# ShutdownSegement.net
KiCad netlist of a schematic drawn in Altium Designer
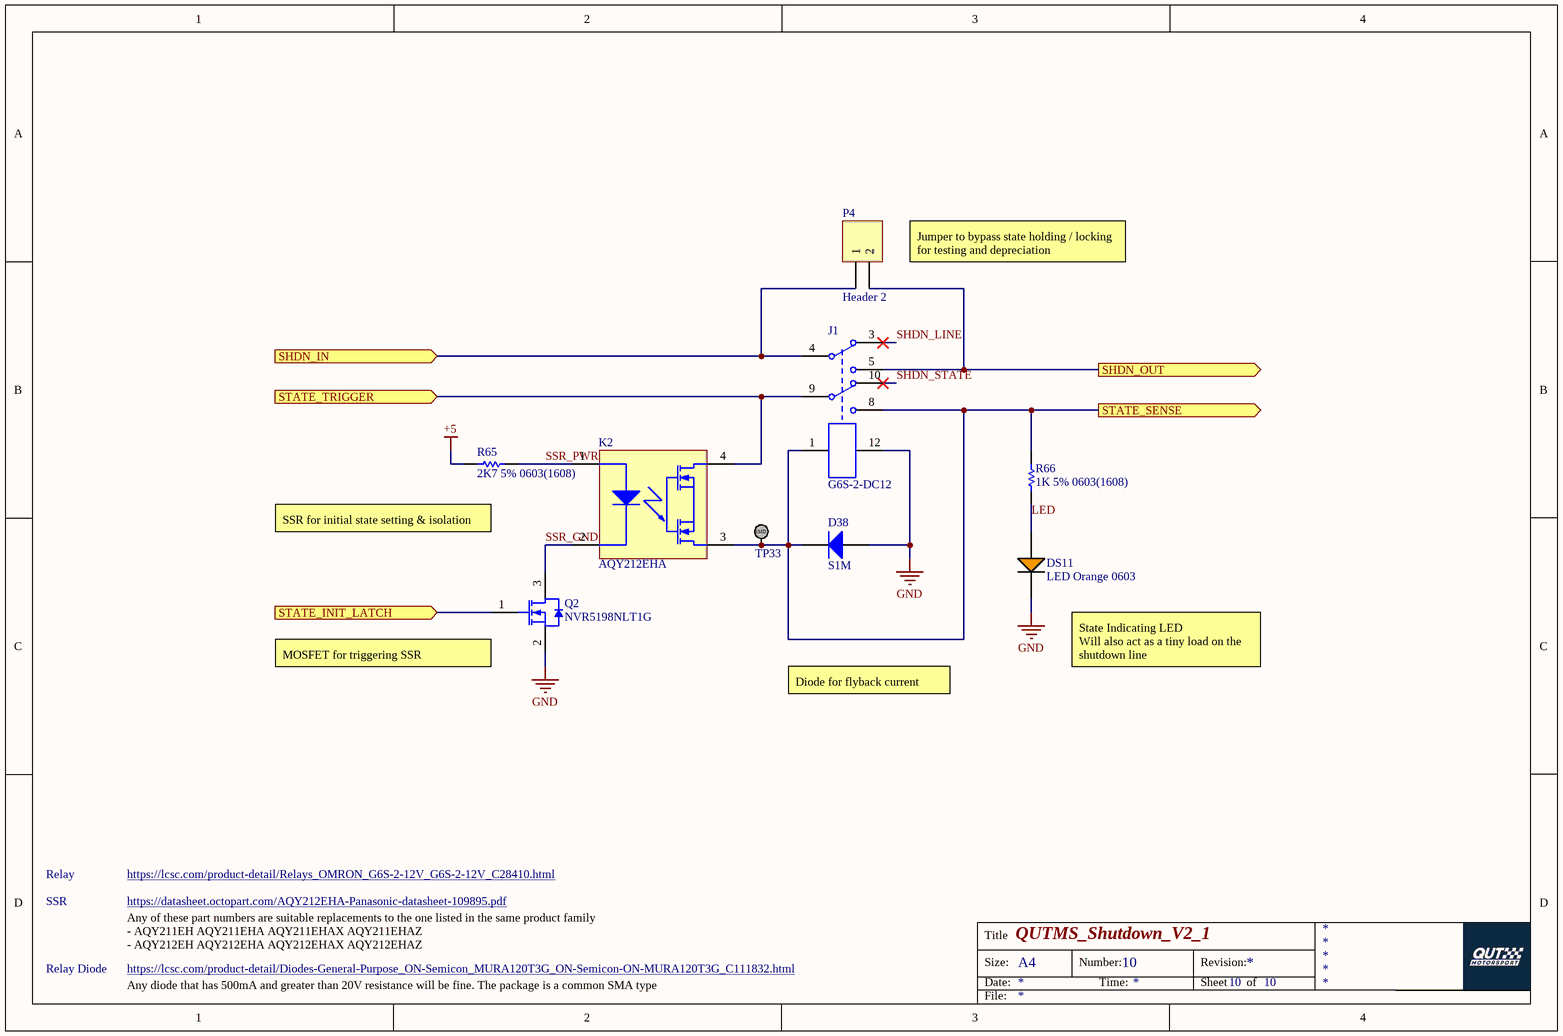
[diagram p0: ShutdownSegement.SchDoc]

(export (version "E")
  (design (tool "Eeschema 10.0.6"))
  (components
    (comp (ref "D38")
      (value "S1M")
      (footprint "FAIR-DO-214AC-2_V")
      (description "General Purpose Rectifier, 1 A, 1000 V, -55 to 150 degC, 2-Pin DO-214AC, RoHS, Tape and Reel")
      (fields (field (name "MANUFACTURER") "Fairchild"))
      (libsource (lib "Altium Content Vault") (part "D-AK-2"))
    )
    (comp (ref "DS11")
      (value "LED Orange 0603")
      (footprint "LED ORANGE 0603")
      (libsource (lib "QUTMS_LEDLibrary") (part "LED ORANGE 0603"))
    )
    (comp (ref "J1")
      (value "G6S-2-DC12")
      (footprint "G6S-2")
      (description "Telecom Non Latching 12VDC DPDT 2A Through Hole Relays RoHS")
      (libsource (lib "QUTMS_RelayLibrary") (part "G6S-2-DC12"))
    )
    (comp (ref "K2")
      (value "AQY212EHA")
      (footprint "PNSC-DIP4(SMT)_V")
      (fields (field (name "MANUFACTURER") "Panasonic"))
      (libsource (lib "Altium Content Vault") (part "PNSC-AQY212EH-DIP4"))
    )
    (comp (ref "P4")
      (value "Header 2")
      (footprint "HDR1X2")
      (description "Header, 2-Pin")
      (fields (field (name "PUBLISHER") "Altium Limited"))
      (libsource (lib "Miscellaneous Connectors") (part "Header 2"))
    )
    (comp (ref "Q2")
      (value "NVR5198NLT1G")
      (footprint "ONSC-SOT-23-3-318-08_V")
      (description "Power MOSFET, 60 V, 155 mOhm, Single N-Channel Logic Level, 3-Pin SOT-23, Pb-Free, Tape and Reel")
      (fields (field (name "MANUFACTURER") "On Semiconductor"))
      (libsource (lib "Altium Content Vault") (part "ONSC-NMOS-G1S2D3-3"))
    )
    (comp (ref "R65")
      (value "2K7 5% 0603(1608)")
      (footprint "RESC0603(1608)_M")
      (description "2K7 0.1W 5% 0603 (1608 Metric)  SMD")
      (fields (field (name "TOLERANCE") "5 %") (field (name "POWER") "0.1 W"))
      (libsource (lib "Altium Content Vault") (part "RES"))
    )
    (comp (ref "R66")
      (value "1K 5% 0603(1608)")
      (footprint "RESC0603(1608)_L")
      (description "1K 0.1W 5% 0603 (1608 Metric)  SMD")
      (fields (field (name "TOLERANCE") "5 %") (field (name "POWER") "0.1 W"))
      (libsource (lib "Altium Content Vault") (part "RES"))
    )
    (comp (ref "TP33")
      (value "TestPoint_SMD")
      (footprint "TestPointSMD")
      (libsource (lib "StandardTest") (part "TestPoint_SMD"))
    )
  )
  (nets
    (net (code "1") (name "+5") (class "Default")
      (node (ref "R65") (pin "1") (pinfunction "1_1") (pintype "passive"))
    )
    (net (code "2") (name "/LED") (class "Default")
      (node (ref "DS11") (pin "1") (pinfunction "A_1") (pintype "passive"))
      (node (ref "R66") (pin "1") (pinfunction "1_1") (pintype "passive"))
    )
    (net (code "3") (name "/SHDN_IN") (class "Default")
      (node (ref "J1") (pin "4") (pinfunction "4_4") (pintype "passive"))
      (node (ref "P4") (pin "1") (pinfunction "1_1") (pintype "passive"))
    )
    (net (code "4") (name "/SHDN_LINE") (class "Default")
      (node (ref "J1") (pin "3") (pinfunction "3_3") (pintype "passive+no_connect"))
    )
    (net (code "5") (name "/SHDN_OUT") (class "Default")
      (node (ref "J1") (pin "5") (pinfunction "5_5") (pintype "passive"))
      (node (ref "P4") (pin "2") (pinfunction "2_2") (pintype "passive"))
    )
    (net (code "6") (name "/SHDN_STATE") (class "Default")
      (node (ref "J1") (pin "10") (pinfunction "10_10") (pintype "passive+no_connect"))
    )
    (net (code "7") (name "/SSR_GND") (class "Default")
      (node (ref "K2") (pin "2") (pinfunction "2_2") (pintype "passive"))
      (node (ref "Q2") (pin "3") (pinfunction "D_3") (pintype "passive"))
    )
    (net (code "8") (name "/SSR_PWR") (class "Default")
      (node (ref "K2") (pin "1") (pinfunction "1_1") (pintype "passive"))
      (node (ref "R65") (pin "2") (pinfunction "2_2") (pintype "passive"))
    )
    (net (code "9") (name "/STATE_INIT_LATCH") (class "Default")
      (node (ref "Q2") (pin "1") (pinfunction "G_1") (pintype "passive"))
    )
    (net (code "10") (name "/STATE_SENSE") (class "Default")
      (node (ref "D38") (pin "2") (pinfunction "K_2") (pintype "passive"))
      (node (ref "J1") (pin "1") (pinfunction "1_1") (pintype "passive"))
      (node (ref "J1") (pin "8") (pinfunction "8_8") (pintype "passive"))
      (node (ref "K2") (pin "3") (pinfunction "3_3") (pintype "passive"))
      (node (ref "R66") (pin "2") (pinfunction "2_2") (pintype "passive"))
      (node (ref "TP33") (pin "1") (pinfunction "1_1") (pintype "passive"))
    )
    (net (code "11") (name "/STATE_TRIGGER") (class "Default")
      (node (ref "J1") (pin "9") (pinfunction "9_9") (pintype "passive"))
      (node (ref "K2") (pin "4") (pinfunction "4_4") (pintype "passive"))
    )
    (net (code "12") (name "GND") (class "Default")
      (node (ref "D38") (pin "1") (pinfunction "A_1") (pintype "passive"))
      (node (ref "DS11") (pin "2") (pinfunction "C_2") (pintype "passive"))
      (node (ref "J1") (pin "12") (pinfunction "12_12") (pintype "passive"))
      (node (ref "Q2") (pin "2") (pinfunction "S_2") (pintype "passive"))
    )
  )
)
